# INL.net
KiCad netlist of a schematic drawn in Altium Designer
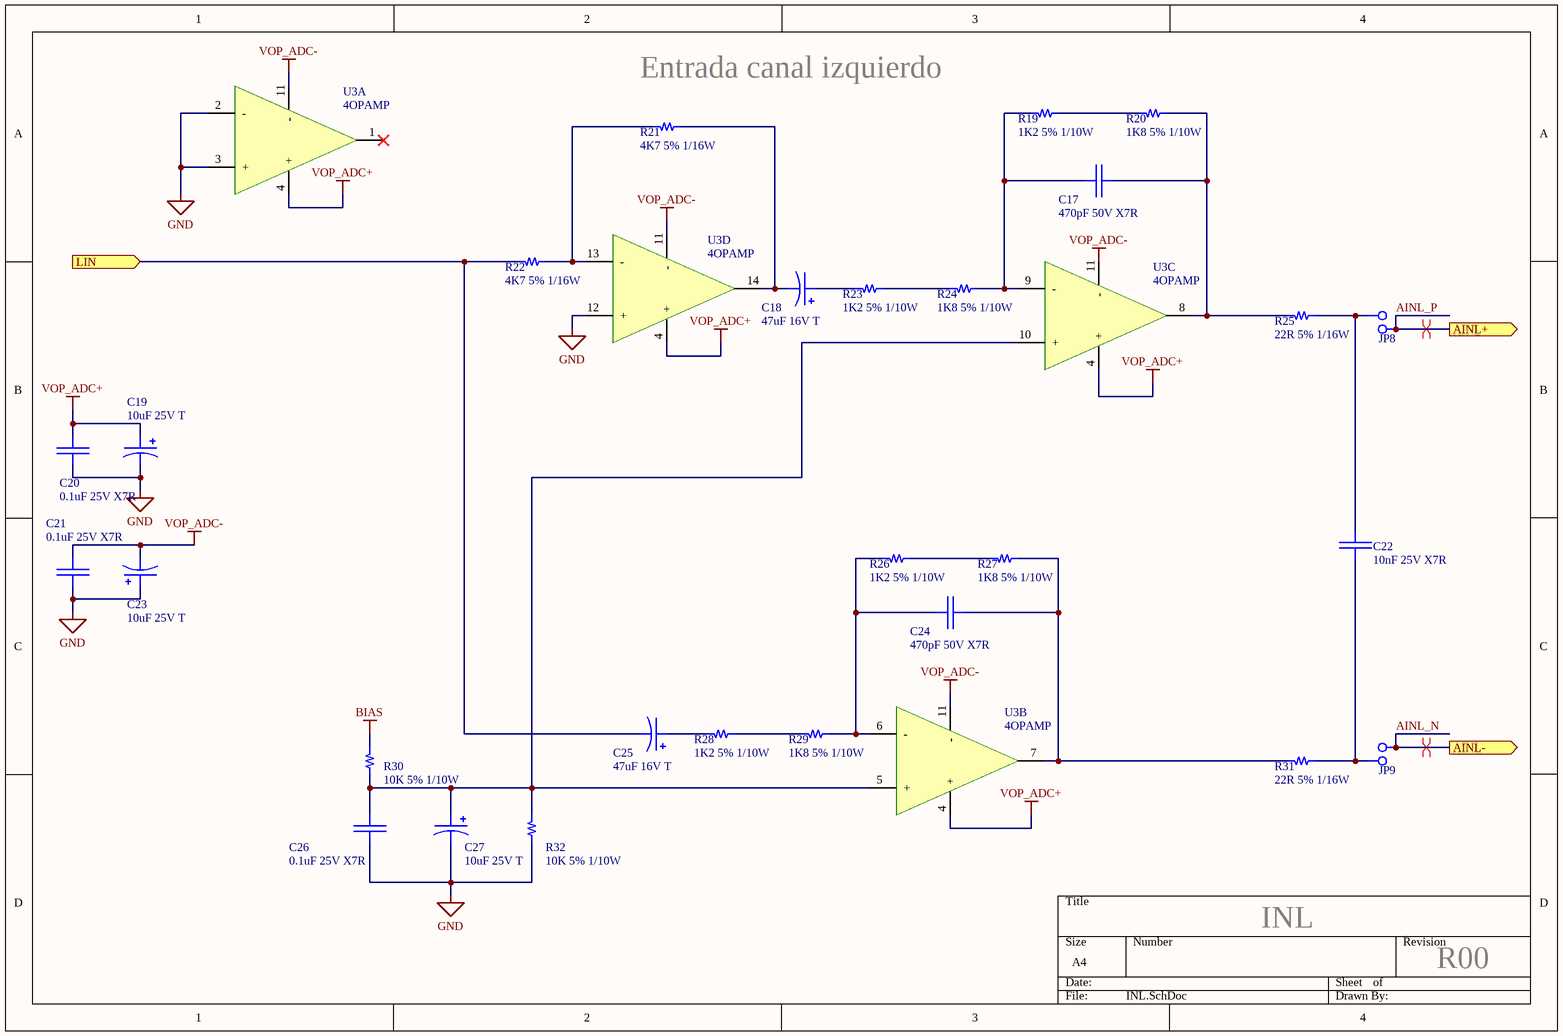
[diagram p0: INL.SchDoc]

(export (version "E")
  (design (tool "Eeschema 10.0.6"))
  (components
    (comp (ref "C17")
      (value "470pF 50V X7R")
      (footprint "C_0805")
      (description "Capacitor de placas paralelas")
      (libsource (lib "Radios_Comunitarias") (part "Capacitor"))
    )
    (comp (ref "C18")
      (value "47uF 16V T")
      (footprint "TANT")
      (description "Capacitor polarizado")
      (libsource (lib "Radios_Comunitarias") (part "CapaPol"))
    )
    (comp (ref "C19")
      (value "10uF 25V T")
      (footprint "TANT")
      (description "Capacitor polarizado")
      (libsource (lib "") (part "CapaPol_1"))
    )
    (comp (ref "C20")
      (value "0.1uF 25V X7R")
      (footprint "C_0805")
      (description "Capacitor de placas paralelas")
      (libsource (lib "Radios_Comunitarias") (part "Capacitor"))
    )
    (comp (ref "C21")
      (value "0.1uF 25V X7R")
      (footprint "C_0805")
      (description "Capacitor de placas paralelas")
      (libsource (lib "Radios_Comunitarias") (part "Capacitor"))
    )
    (comp (ref "C22")
      (value "10nF 25V X7R")
      (footprint "C_0805")
      (description "Capacitor de placas paralelas")
      (libsource (lib "Radios_Comunitarias") (part "Capacitor"))
    )
    (comp (ref "C23")
      (value "10uF 25V T")
      (footprint "TANT")
      (description "Capacitor polarizado")
      (libsource (lib "") (part "CapaPol_1"))
    )
    (comp (ref "C24")
      (value "470pF 50V X7R")
      (footprint "C_0805")
      (description "Capacitor de placas paralelas")
      (libsource (lib "Radios_Comunitarias") (part "Capacitor"))
    )
    (comp (ref "C25")
      (value "47uF 16V T")
      (footprint "TANT")
      (description "Capacitor polarizado")
      (libsource (lib "Radios_Comunitarias") (part "CapaPol"))
    )
    (comp (ref "C26")
      (value "0.1uF 25V X7R")
      (footprint "C_0805")
      (description "Capacitor de placas paralelas")
      (libsource (lib "Radios_Comunitarias") (part "Capacitor"))
    )
    (comp (ref "C27")
      (value "10uF 25V T")
      (footprint "TANT")
      (description "Capacitor polarizado")
      (libsource (lib "") (part "CapaPol_1"))
    )
    (comp (ref "JP8")
      (value "Jumper 2x1")
      (footprint "Conn_2_1")
      (libsource (lib "Radios_Comunitarias") (part "Jumper 2x1"))
    )
    (comp (ref "JP9")
      (value "Jumper 2x1")
      (footprint "Conn_2_1")
      (libsource (lib "Radios_Comunitarias") (part "Jumper 2x1"))
    )
    (comp (ref "R19")
      (value "1K2 5% 1/10W")
      (footprint "R_0805")
      (description "Resistencia")
      (libsource (lib "Radios_Comunitarias") (part "Resistor"))
    )
    (comp (ref "R20")
      (value "1K8 5% 1/10W")
      (footprint "R_0805")
      (description "Resistencia")
      (libsource (lib "Radios_Comunitarias") (part "Resistor"))
    )
    (comp (ref "R21")
      (value "4K7 5% 1/16W")
      (footprint "R_0805")
      (description "Resistencia")
      (libsource (lib "Radios_Comunitarias") (part "Resistor"))
    )
    (comp (ref "R22")
      (value "4K7 5% 1/16W")
      (footprint "R_0805")
      (description "Resistencia")
      (libsource (lib "Radios_Comunitarias") (part "Resistor"))
    )
    (comp (ref "R23")
      (value "1K2 5% 1/10W")
      (footprint "R_0805")
      (description "Resistencia")
      (libsource (lib "Radios_Comunitarias") (part "Resistor"))
    )
    (comp (ref "R24")
      (value "1K8 5% 1/10W")
      (footprint "R_0805")
      (description "Resistencia")
      (libsource (lib "Radios_Comunitarias") (part "Resistor"))
    )
    (comp (ref "R25")
      (value "22R 5% 1/16W")
      (footprint "R_0805")
      (description "Resistencia")
      (libsource (lib "Radios_Comunitarias") (part "Resistor"))
    )
    (comp (ref "R26")
      (value "1K2 5% 1/10W")
      (footprint "R_0805")
      (description "Resistencia")
      (libsource (lib "Radios_Comunitarias") (part "Resistor"))
    )
    (comp (ref "R27")
      (value "1K8 5% 1/10W")
      (footprint "R_0805")
      (description "Resistencia")
      (libsource (lib "Radios_Comunitarias") (part "Resistor"))
    )
    (comp (ref "R28")
      (value "1K2 5% 1/10W")
      (footprint "R_0805")
      (description "Resistencia")
      (libsource (lib "Radios_Comunitarias") (part "Resistor"))
    )
    (comp (ref "R29")
      (value "1K8 5% 1/10W")
      (footprint "R_0805")
      (description "Resistencia")
      (libsource (lib "Radios_Comunitarias") (part "Resistor"))
    )
    (comp (ref "R30")
      (value "10K 5% 1/10W")
      (footprint "R_0805")
      (description "Resistencia")
      (libsource (lib "Radios_Comunitarias") (part "Resistor"))
    )
    (comp (ref "R31")
      (value "22R 5% 1/16W")
      (footprint "R_0805")
      (description "Resistencia")
      (libsource (lib "Radios_Comunitarias") (part "Resistor"))
    )
    (comp (ref "R32")
      (value "10K 5% 1/10W")
      (footprint "R_0805")
      (description "Resistencia")
      (libsource (lib "Radios_Comunitarias") (part "Resistor"))
    )
    (comp (ref "U3")
      (value "4OPAMP")
      (footprint "SOIC14")
      (description "Integrado con 4 operacionales")
      (libsource (lib "Radios_Comunitarias") (part "4OPAMP"))
    )
  )
  (nets
    (net (code "1") (name "/AINL_N") (class "Default")
      (node (ref "JP9") (pin "1") (pinfunction "1_1") (pintype "passive"))
    )
    (net (code "2") (name "/AINL_P") (class "Default")
      (node (ref "JP8") (pin "2") (pinfunction "2_2") (pintype "passive"))
    )
    (net (code "3") (name "/LIN") (class "Default")
      (node (ref "C25") (pin "2") (pinfunction "2_2") (pintype "passive"))
      (node (ref "R22") (pin "2") (pinfunction "2_2") (pintype "passive"))
    )
    (net (code "4") (name "BIAS") (class "Default")
      (node (ref "R30") (pin "2") (pinfunction "2_2") (pintype "passive"))
    )
    (net (code "5") (name "GND") (class "Default")
      (node (ref "C19") (pin "2") (pinfunction "2_2") (pintype "passive"))
      (node (ref "C20") (pin "2") (pinfunction "2_2") (pintype "passive"))
      (node (ref "C21") (pin "2") (pinfunction "2_2") (pintype "passive"))
      (node (ref "C23") (pin "1") (pinfunction "1_1") (pintype "passive"))
      (node (ref "C26") (pin "2") (pinfunction "2_2") (pintype "passive"))
      (node (ref "C27") (pin "2") (pinfunction "2_2") (pintype "passive"))
      (node (ref "R32") (pin "1") (pinfunction "1_1") (pintype "passive"))
      (node (ref "U3") (pin "12") (pinfunction "+_12") (pintype "passive"))
      (node (ref "U3") (pin "2") (pinfunction "-_2") (pintype "passive"))
      (node (ref "U3") (pin "3") (pinfunction "+_3") (pintype "passive"))
    )
    (net (code "6") (name "Net-(C17-Pad1)") (class "Default")
      (node (ref "C17") (pin "1") (pinfunction "1_1") (pintype "passive"))
      (node (ref "R19") (pin "2") (pinfunction "2_2") (pintype "passive"))
      (node (ref "R24") (pin "1") (pinfunction "1_1") (pintype "passive"))
      (node (ref "U3") (pin "9") (pinfunction "-_9") (pintype "passive"))
    )
    (net (code "7") (name "Net-(C18-Pad1)") (class "Default")
      (node (ref "C18") (pin "1") (pinfunction "1_1") (pintype "passive"))
      (node (ref "R23") (pin "2") (pinfunction "2_2") (pintype "passive"))
    )
    (net (code "8") (name "Net-(C22-Pad1)") (class "Default")
      (node (ref "C22") (pin "1") (pinfunction "1_1") (pintype "passive"))
      (node (ref "JP9") (pin "2") (pinfunction "2_2") (pintype "passive"))
      (node (ref "R31") (pin "1") (pinfunction "1_1") (pintype "passive"))
    )
    (net (code "9") (name "Net-(C22-Pad2)") (class "Default")
      (node (ref "C22") (pin "2") (pinfunction "2_2") (pintype "passive"))
      (node (ref "JP8") (pin "1") (pinfunction "1_1") (pintype "passive"))
      (node (ref "R25") (pin "1") (pinfunction "1_1") (pintype "passive"))
    )
    (net (code "10") (name "Net-(C24-Pad1)") (class "Default")
      (node (ref "C24") (pin "1") (pinfunction "1_1") (pintype "passive"))
      (node (ref "R26") (pin "2") (pinfunction "2_2") (pintype "passive"))
      (node (ref "R29") (pin "1") (pinfunction "1_1") (pintype "passive"))
      (node (ref "U3") (pin "6") (pinfunction "-_6") (pintype "passive"))
    )
    (net (code "11") (name "Net-(C25-Pad1)") (class "Default")
      (node (ref "C25") (pin "1") (pinfunction "1_1") (pintype "passive"))
      (node (ref "R28") (pin "2") (pinfunction "2_2") (pintype "passive"))
    )
    (net (code "12") (name "Net-(C26-Pad1)") (class "Default")
      (node (ref "C26") (pin "1") (pinfunction "1_1") (pintype "passive"))
      (node (ref "C27") (pin "1") (pinfunction "1_1") (pintype "passive"))
      (node (ref "R30") (pin "1") (pinfunction "1_1") (pintype "passive"))
      (node (ref "R32") (pin "2") (pinfunction "2_2") (pintype "passive"))
      (node (ref "U3") (pin "10") (pinfunction "+_10") (pintype "passive"))
      (node (ref "U3") (pin "5") (pinfunction "+_5") (pintype "passive"))
    )
    (net (code "13") (name "Net-(R19-Pad1)") (class "Default")
      (node (ref "R19") (pin "1") (pinfunction "1_1") (pintype "passive"))
      (node (ref "R20") (pin "2") (pinfunction "2_2") (pintype "passive"))
    )
    (net (code "14") (name "Net-(R21-Pad2)") (class "Default")
      (node (ref "R21") (pin "2") (pinfunction "2_2") (pintype "passive"))
      (node (ref "R22") (pin "1") (pinfunction "1_1") (pintype "passive"))
      (node (ref "U3") (pin "13") (pinfunction "-_13") (pintype "passive"))
    )
    (net (code "15") (name "Net-(R23-Pad1)") (class "Default")
      (node (ref "R23") (pin "1") (pinfunction "1_1") (pintype "passive"))
      (node (ref "R24") (pin "2") (pinfunction "2_2") (pintype "passive"))
    )
    (net (code "16") (name "Net-(R26-Pad1)") (class "Default")
      (node (ref "R26") (pin "1") (pinfunction "1_1") (pintype "passive"))
      (node (ref "R27") (pin "2") (pinfunction "2_2") (pintype "passive"))
    )
    (net (code "17") (name "Net-(R28-Pad1)") (class "Default")
      (node (ref "R28") (pin "1") (pinfunction "1_1") (pintype "passive"))
      (node (ref "R29") (pin "2") (pinfunction "2_2") (pintype "passive"))
    )
    (net (code "18") (name "Net-(U3B-OUT)") (class "Default")
      (node (ref "C24") (pin "2") (pinfunction "2_2") (pintype "passive"))
      (node (ref "R27") (pin "1") (pinfunction "1_1") (pintype "passive"))
      (node (ref "R31") (pin "2") (pinfunction "2_2") (pintype "passive"))
      (node (ref "U3") (pin "7") (pinfunction "OUT_7") (pintype "passive"))
    )
    (net (code "19") (name "Net-(U3C-OUT)") (class "Default")
      (node (ref "C17") (pin "2") (pinfunction "2_2") (pintype "passive"))
      (node (ref "R20") (pin "1") (pinfunction "1_1") (pintype "passive"))
      (node (ref "R25") (pin "2") (pinfunction "2_2") (pintype "passive"))
      (node (ref "U3") (pin "8") (pinfunction "OUT_8") (pintype "passive"))
    )
    (net (code "20") (name "Net-(U3D-OUT)") (class "Default")
      (node (ref "C18") (pin "2") (pinfunction "2_2") (pintype "passive"))
      (node (ref "R21") (pin "1") (pinfunction "1_1") (pintype "passive"))
      (node (ref "U3") (pin "14") (pinfunction "OUT_14") (pintype "passive"))
    )
    (net (code "21") (name "VOP_ADC+") (class "Default")
      (node (ref "C19") (pin "1") (pinfunction "1_1") (pintype "passive"))
      (node (ref "C20") (pin "1") (pinfunction "1_1") (pintype "passive"))
      (node (ref "U3") (pin "4") (pinfunction "+_4") (pintype "power_in"))
    )
    (net (code "22") (name "VOP_ADC-") (class "Default")
      (node (ref "C21") (pin "1") (pinfunction "1_1") (pintype "passive"))
      (node (ref "C23") (pin "2") (pinfunction "2_2") (pintype "passive"))
      (node (ref "U3") (pin "11") (pinfunction "-_11") (pintype "passive"))
    )
    (net (code "23") (name "unconnected-(U3A-OUT-Pad1)") (class "Default")
      (node (ref "U3") (pin "1") (pinfunction "OUT_1") (pintype "passive+no_connect"))
    )
  )
)
